# Cytrill.net
KiCad netlist of a schematic drawn in EAGLE
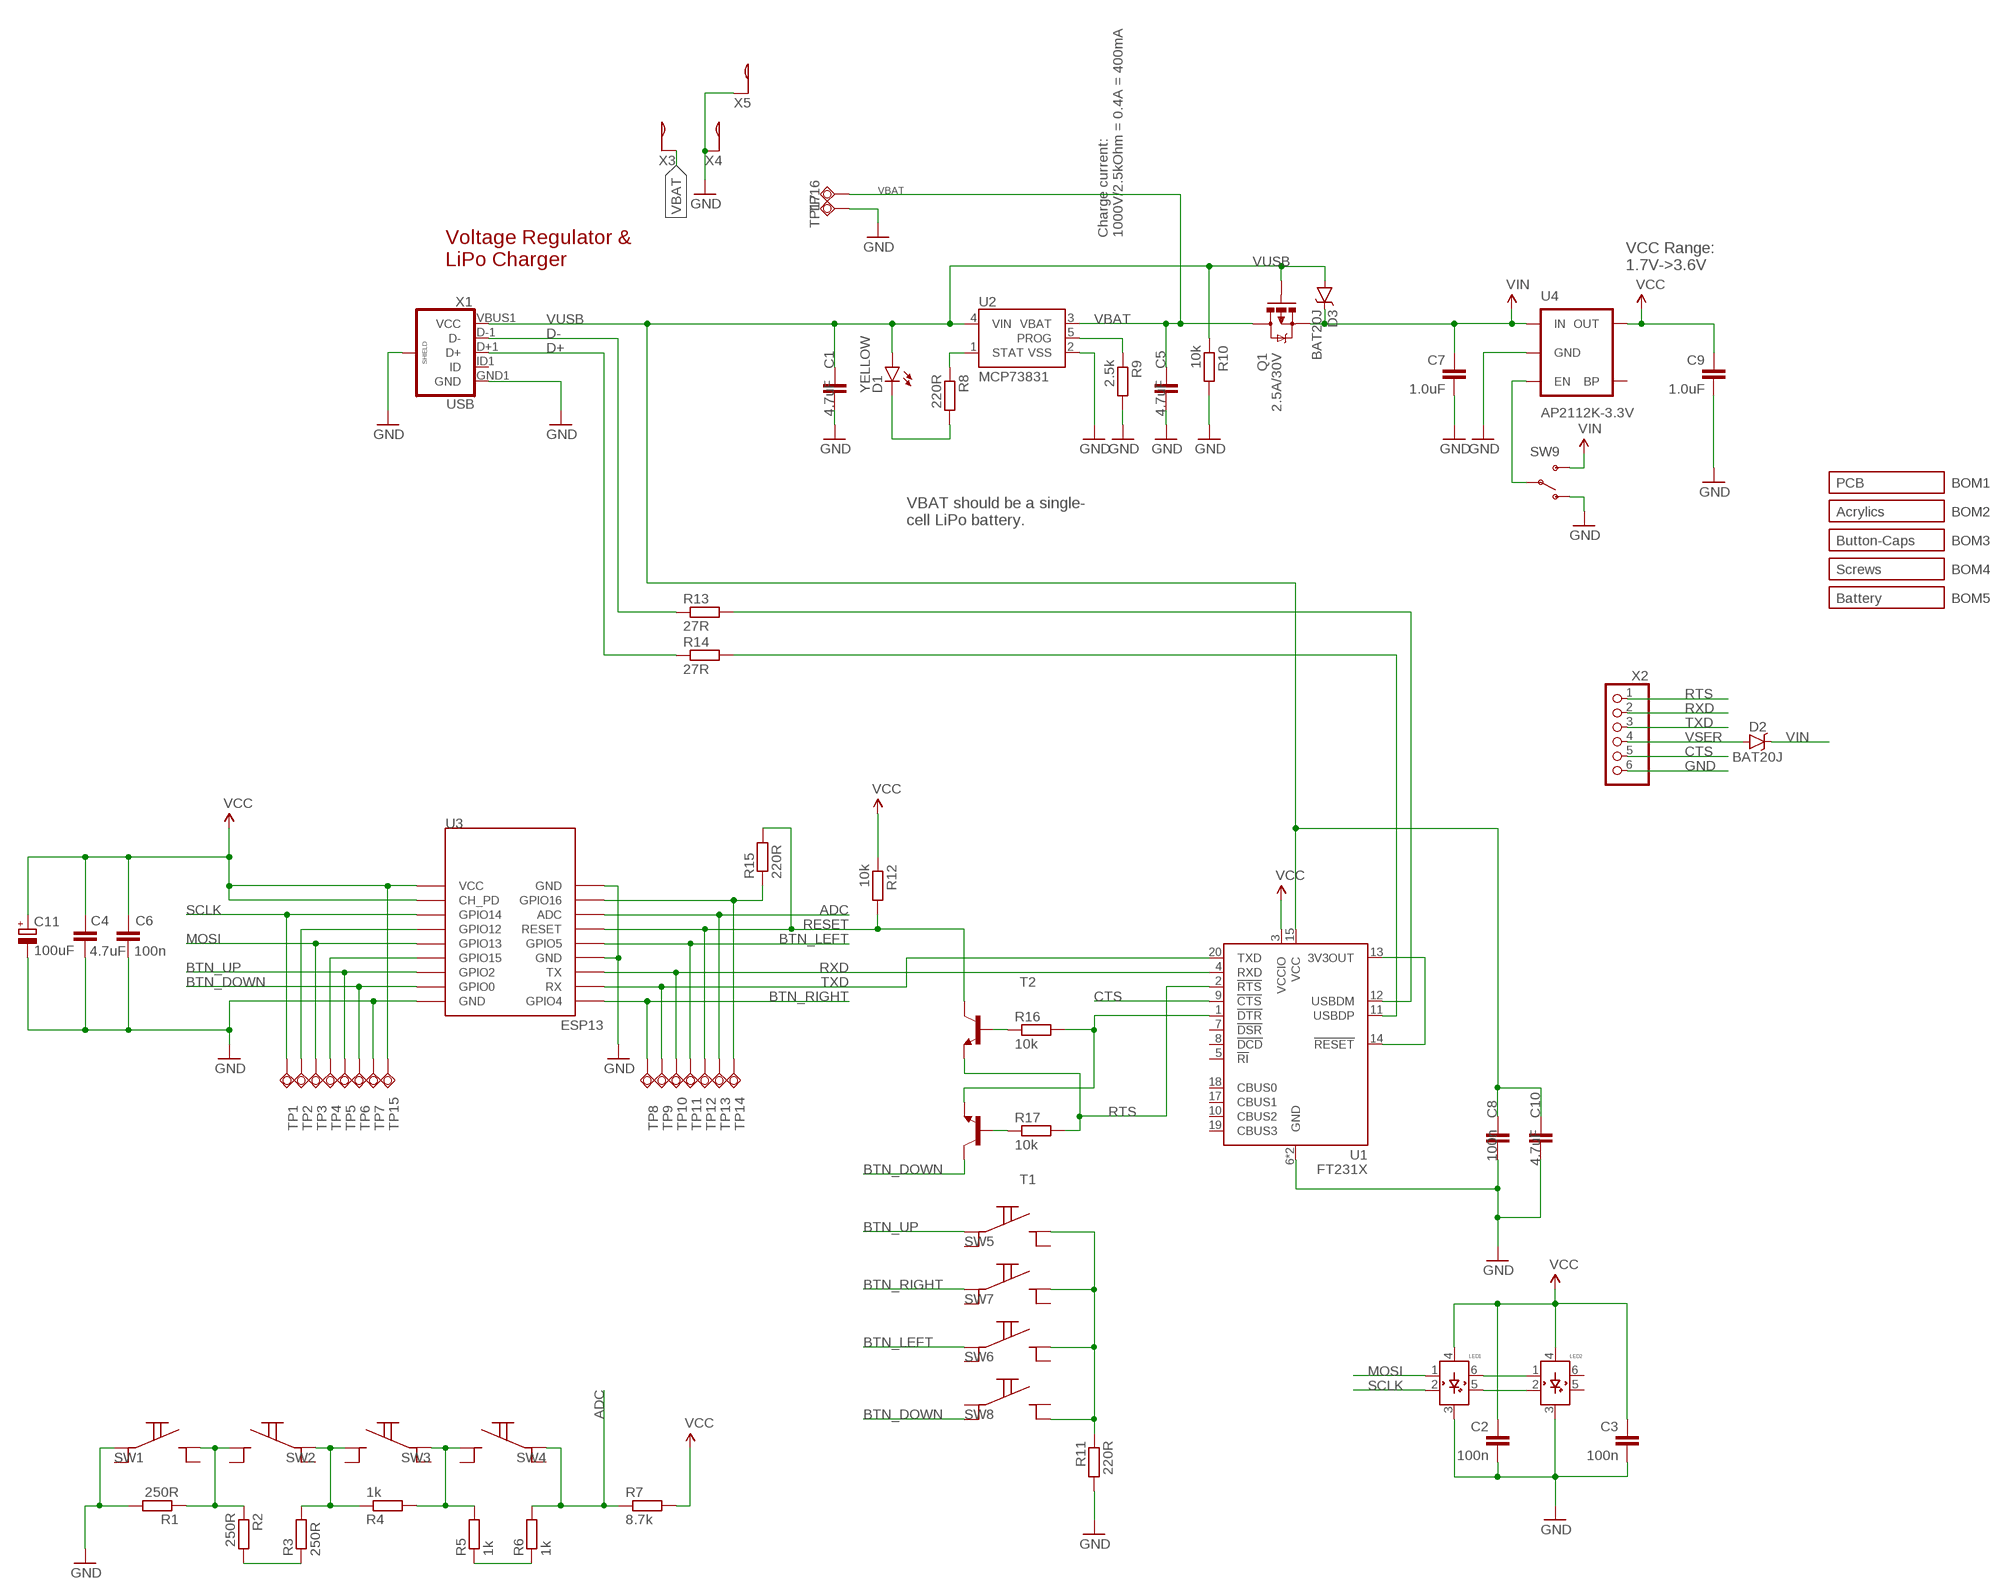
[diagram p0: schematic, sheet 1]

(export (version "E")
  (design (tool "Eeschema 10.0.6"))
  (components
    (comp (ref "C1")
      (value "4.7uF")
      (footprint "eagle-import:C0603")
      (fields (field (name "PARTNO") "GRM188R61A475KE15D-MO"))
      (libsource (lib "eagle-import") (part "C-EUC0603"))
    )
    (comp (ref "C2")
      (value "100n")
      (footprint "eagle-import:C0603")
      (fields (field (name "PARTNO") "C0603C104K4RACTU-MO"))
      (libsource (lib "eagle-import") (part "C-EUC0603"))
    )
    (comp (ref "C3")
      (value "100n")
      (footprint "eagle-import:C0603")
      (fields (field (name "PARTNO") "C0603C104K4RACTU-MO"))
      (libsource (lib "eagle-import") (part "C-EUC0603"))
    )
    (comp (ref "C4")
      (value "4.7uF")
      (footprint "eagle-import:C0603")
      (fields (field (name "PARTNO") "GRM188R61A475KE15D-MO"))
      (libsource (lib "eagle-import") (part "C-EUC0603"))
    )
    (comp (ref "C5")
      (value "4.7uF")
      (footprint "eagle-import:C0603")
      (fields (field (name "PARTNO") "GRM188R61A475KE15D-MO"))
      (libsource (lib "eagle-import") (part "C-EUC0603"))
    )
    (comp (ref "C6")
      (value "100n")
      (footprint "eagle-import:C0603")
      (fields (field (name "PARTNO") "C0603C104K4RACTU-MO"))
      (libsource (lib "eagle-import") (part "C-EUC0603"))
    )
    (comp (ref "C7")
      (value "1.0uF")
      (footprint "eagle-import:C0603")
      (fields (field (name "PARTNO") "GRM188R61E105KA12D-MO"))
      (libsource (lib "eagle-import") (part "C-EUC0603"))
    )
    (comp (ref "C8")
      (value "100n")
      (footprint "eagle-import:C0603")
      (fields (field (name "PARTNO") "C0603C104K4RACTU-MO"))
      (libsource (lib "eagle-import") (part "C-EUC0603"))
    )
    (comp (ref "C9")
      (value "1.0uF")
      (footprint "eagle-import:C0603")
      (fields (field (name "PARTNO") "GRM188R61E105KA12D-MO"))
      (libsource (lib "eagle-import") (part "C-EUC0603"))
    )
    (comp (ref "C10")
      (value "4.7uF")
      (footprint "eagle-import:C0603")
      (fields (field (name "PARTNO") "GRM188R61A475KE15D-MO"))
      (libsource (lib "eagle-import") (part "C-EUC0603"))
    )
    (comp (ref "C11")
      (value "100uF")
      (footprint "eagle-import:3216-A")
      (fields (field (name "PARTNO") "TANTAL100UF"))
      (libsource (lib "eagle-import") (part "CPOL-EU085CS-1AR"))
    )
    (comp (ref "D1")
      (value "YELLOW")
      (footprint "eagle-import:LED-0603")
      (fields (field (name "PARTNO") "LYQ396P1Q236-MO"))
      (libsource (lib "eagle-import") (part "LED-YELLOW0603"))
    )
    (comp (ref "D2")
      (value "BAT20J")
      (footprint "eagle-import:SOD-323")
      (fields (field (name "PARTNO") "BAT20JFILM-MO"))
      (libsource (lib "eagle-import") (part "DIODE-SCHOTTKY-BAT20J"))
    )
    (comp (ref "D3")
      (value "BAT20J")
      (footprint "eagle-import:SOD-323")
      (fields (field (name "PARTNO") "BAT20JFILM-MO"))
      (libsource (lib "eagle-import") (part "DIODE-SCHOTTKY-BAT20J"))
    )
    (comp (ref "LED1")
      (value "APA102")
      (footprint "eagle-import:RGBLED5050")
      (libsource (lib "eagle-import") (part "APA102"))
    )
    (comp (ref "LED2")
      (value "APA102")
      (footprint "eagle-import:RGBLED5050")
      (libsource (lib "eagle-import") (part "APA102"))
    )
    (comp (ref "Q1")
      (value "2.5A/30V")
      (footprint "eagle-import:SOT23-3")
      (fields (field (name "PARTNO") "DMP3130L-7-MO"))
      (libsource (lib "eagle-import") (part "MOSFET-PCHANNELDMG2307L"))
    )
    (comp (ref "R1")
      (value "250R")
      (footprint "eagle-import:R0603")
      (fields (field (name "PARTNO") "ERJ3EKF2490V-MO"))
      (libsource (lib "eagle-import") (part "R-EU_R0603"))
    )
    (comp (ref "R2")
      (value "250R")
      (footprint "eagle-import:R0603")
      (fields (field (name "PARTNO") "ERJ3EKF2490V-MO"))
      (libsource (lib "eagle-import") (part "R-EU_R0603"))
    )
    (comp (ref "R3")
      (value "250R")
      (footprint "eagle-import:R0603")
      (fields (field (name "PARTNO") "ERJ3EKF2490V-MO"))
      (libsource (lib "eagle-import") (part "R-EU_R0603"))
    )
    (comp (ref "R4")
      (value "1k")
      (footprint "eagle-import:R0603")
      (fields (field (name "PARTNO") "ERJ3EKF1001V-MO"))
      (libsource (lib "eagle-import") (part "R-EU_R0603"))
    )
    (comp (ref "R5")
      (value "1k")
      (footprint "eagle-import:R0603")
      (fields (field (name "PARTNO") "ERJ3EKF1001V-MO"))
      (libsource (lib "eagle-import") (part "R-EU_R0603"))
    )
    (comp (ref "R6")
      (value "1k")
      (footprint "eagle-import:R0603")
      (fields (field (name "PARTNO") "ERJ3EKF1001V-MO"))
      (libsource (lib "eagle-import") (part "R-EU_R0603"))
    )
    (comp (ref "R7")
      (value "8.7k")
      (footprint "eagle-import:R0603")
      (fields (field (name "PARTNO") "ERJ3EKF8661V-MO"))
      (libsource (lib "eagle-import") (part "R-EU_R0603"))
    )
    (comp (ref "R8")
      (value "220R")
      (footprint "eagle-import:R0603")
      (fields (field (name "PARTNO") "ERJ3EKF2200V-MO"))
      (libsource (lib "eagle-import") (part "R-EU_R0603"))
    )
    (comp (ref "R9")
      (value "2.5k")
      (footprint "eagle-import:R0603")
      (fields (field (name "PARTNO") "ERJ3EKF2491V-MO"))
      (libsource (lib "eagle-import") (part "R-EU_R0603"))
    )
    (comp (ref "R10")
      (value "10k")
      (footprint "eagle-import:R0603")
      (fields (field (name "PARTNO") "ERJ3EKF1002V-MO"))
      (libsource (lib "eagle-import") (part "R-EU_R0603"))
    )
    (comp (ref "R11")
      (value "220R")
      (footprint "eagle-import:R0603")
      (fields (field (name "PARTNO") "ERJ3EKF2200V-MO"))
      (libsource (lib "eagle-import") (part "R-EU_R0603"))
    )
    (comp (ref "R12")
      (value "10k")
      (footprint "eagle-import:R0603")
      (fields (field (name "PARTNO") "ERJ3EKF1002V-MO"))
      (libsource (lib "eagle-import") (part "R-EU_R0603"))
    )
    (comp (ref "R13")
      (value "27R")
      (footprint "eagle-import:R0603")
      (fields (field (name "PARTNO") "ERJ3EKF27R0V-MO"))
      (libsource (lib "eagle-import") (part "R-EU_R0603"))
    )
    (comp (ref "R14")
      (value "27R")
      (footprint "eagle-import:R0603")
      (fields (field (name "PARTNO") "ERJ3EKF27R0V-MO"))
      (libsource (lib "eagle-import") (part "R-EU_R0603"))
    )
    (comp (ref "R15")
      (value "220R")
      (footprint "eagle-import:R0603")
      (fields (field (name "PARTNO") "ERJ3EKF2200V-MO"))
      (libsource (lib "eagle-import") (part "R-EU_R0603"))
    )
    (comp (ref "R16")
      (value "10k")
      (footprint "eagle-import:R0603")
      (fields (field (name "PARTNO") "ERJ3EKF1002V-MO"))
      (libsource (lib "eagle-import") (part "R-EU_R0603"))
    )
    (comp (ref "R17")
      (value "10k")
      (footprint "eagle-import:R0603")
      (fields (field (name "PARTNO") "ERJ3EKF1002V-MO"))
      (libsource (lib "eagle-import") (part "R-EU_R0603"))
    )
    (comp (ref "SW1")
      (value "TACTSWITCH6MM")
      (footprint "eagle-import:TACTSWITCH")
      (fields (field (name "PARTNO") "101-0364-EV-MO"))
      (libsource (lib "eagle-import") (part "TACTSWITCH6MM"))
    )
    (comp (ref "SW2")
      (value "TACTSWITCH6MM")
      (footprint "eagle-import:TACTSWITCH")
      (fields (field (name "PARTNO") "101-0364-EV-MO"))
      (libsource (lib "eagle-import") (part "TACTSWITCH6MM"))
    )
    (comp (ref "SW3")
      (value "TACTSWITCH6MM")
      (footprint "eagle-import:TACTSWITCH")
      (fields (field (name "PARTNO") "101-0364-EV-MO"))
      (libsource (lib "eagle-import") (part "TACTSWITCH6MM"))
    )
    (comp (ref "SW4")
      (value "TACTSWITCH6MM")
      (footprint "eagle-import:TACTSWITCH")
      (fields (field (name "PARTNO") "101-0364-EV-MO"))
      (libsource (lib "eagle-import") (part "TACTSWITCH6MM"))
    )
    (comp (ref "SW5")
      (value "TACTSWITCH6MM")
      (footprint "eagle-import:TACTSWITCH")
      (fields (field (name "PARTNO") "101-0364-EV-MO"))
      (libsource (lib "eagle-import") (part "TACTSWITCH6MM"))
    )
    (comp (ref "SW6")
      (value "TACTSWITCH6MM")
      (footprint "eagle-import:TACTSWITCH")
      (fields (field (name "PARTNO") "101-0364-EV-MO"))
      (libsource (lib "eagle-import") (part "TACTSWITCH6MM"))
    )
    (comp (ref "SW7")
      (value "TACTSWITCH6MM")
      (footprint "eagle-import:TACTSWITCH")
      (fields (field (name "PARTNO") "101-0364-EV-MO"))
      (libsource (lib "eagle-import") (part "TACTSWITCH6MM"))
    )
    (comp (ref "SW8")
      (value "TACTSWITCH6MM")
      (footprint "eagle-import:TACTSWITCH")
      (fields (field (name "PARTNO") "101-0364-EV-MO"))
      (libsource (lib "eagle-import") (part "TACTSWITCH6MM"))
    )
    (comp (ref "SW9")
      (value "SWITCH-SPDT-SMD-A")
      (footprint "eagle-import:SWITCH-SPST-SMD-A")
      (fields (field (name "PARTNO") "SSSS810701"))
      (libsource (lib "eagle-import") (part "SWITCH-SPDT-SMD-A"))
    )
    (comp (ref "T1")
      (value "BC847C-NPN-SOT23-BEC")
      (footprint "eagle-import:SOT23-BEC")
      (fields (field (name "PARTNO") "BC847C-MO"))
      (libsource (lib "eagle-import") (part "-NPN-SOT23-BECBC847C"))
    )
    (comp (ref "T2")
      (value "BC847C-NPN-SOT23-BEC")
      (footprint "eagle-import:SOT23-BEC")
      (fields (field (name "PARTNO") "BC847C-MO"))
      (libsource (lib "eagle-import") (part "-NPN-SOT23-BECBC847C"))
    )
    (comp (ref "TP1")
      (value "TPSQTP15SQ")
      (footprint "eagle-import:TP15SQ")
      (fields (field (name "PARTNO") "TESTPAD"))
      (libsource (lib "eagle-import") (part "TPSQTP15SQ"))
    )
    (comp (ref "TP2")
      (value "TPSQTP15SQ")
      (footprint "eagle-import:TP15SQ")
      (fields (field (name "PARTNO") "TESTPAD"))
      (libsource (lib "eagle-import") (part "TPSQTP15SQ"))
    )
    (comp (ref "TP3")
      (value "TPSQTP15SQ")
      (footprint "eagle-import:TP15SQ")
      (fields (field (name "PARTNO") "TESTPAD"))
      (libsource (lib "eagle-import") (part "TPSQTP15SQ"))
    )
    (comp (ref "TP4")
      (value "TPSQTP15SQ")
      (footprint "eagle-import:TP15SQ")
      (fields (field (name "PARTNO") "TESTPAD"))
      (libsource (lib "eagle-import") (part "TPSQTP15SQ"))
    )
    (comp (ref "TP5")
      (value "TPSQTP15SQ")
      (footprint "eagle-import:TP15SQ")
      (fields (field (name "PARTNO") "TESTPAD"))
      (libsource (lib "eagle-import") (part "TPSQTP15SQ"))
    )
    (comp (ref "TP6")
      (value "TPSQTP15SQ")
      (footprint "eagle-import:TP15SQ")
      (fields (field (name "PARTNO") "TESTPAD"))
      (libsource (lib "eagle-import") (part "TPSQTP15SQ"))
    )
    (comp (ref "TP7")
      (value "TPSQTP15SQ")
      (footprint "eagle-import:TP15SQ")
      (fields (field (name "PARTNO") "TESTPAD"))
      (libsource (lib "eagle-import") (part "TPSQTP15SQ"))
    )
    (comp (ref "TP8")
      (value "TPSQTP15SQ")
      (footprint "eagle-import:TP15SQ")
      (fields (field (name "PARTNO") "TESTPAD"))
      (libsource (lib "eagle-import") (part "TPSQTP15SQ"))
    )
    (comp (ref "TP9")
      (value "TPSQTP15SQ")
      (footprint "eagle-import:TP15SQ")
      (fields (field (name "PARTNO") "TESTPAD"))
      (libsource (lib "eagle-import") (part "TPSQTP15SQ"))
    )
    (comp (ref "TP10")
      (value "TPSQTP15SQ")
      (footprint "eagle-import:TP15SQ")
      (fields (field (name "PARTNO") "TESTPAD"))
      (libsource (lib "eagle-import") (part "TPSQTP15SQ"))
    )
    (comp (ref "TP11")
      (value "TPSQTP15SQ")
      (footprint "eagle-import:TP15SQ")
      (fields (field (name "PARTNO") "TESTPAD"))
      (libsource (lib "eagle-import") (part "TPSQTP15SQ"))
    )
    (comp (ref "TP12")
      (value "TPSQTP15SQ")
      (footprint "eagle-import:TP15SQ")
      (fields (field (name "PARTNO") "TESTPAD"))
      (libsource (lib "eagle-import") (part "TPSQTP15SQ"))
    )
    (comp (ref "TP13")
      (value "TPSQTP15SQ")
      (footprint "eagle-import:TP15SQ")
      (fields (field (name "PARTNO") "TESTPAD"))
      (libsource (lib "eagle-import") (part "TPSQTP15SQ"))
    )
    (comp (ref "TP14")
      (value "TPSQTP15SQ")
      (footprint "eagle-import:TP15SQ")
      (fields (field (name "PARTNO") "TESTPAD"))
      (libsource (lib "eagle-import") (part "TPSQTP15SQ"))
    )
    (comp (ref "TP15")
      (value "TPSQTP15SQ")
      (footprint "eagle-import:TP15SQ")
      (fields (field (name "PARTNO") "TESTPAD"))
      (libsource (lib "eagle-import") (part "TPSQTP15SQ"))
    )
    (comp (ref "TP16")
      (value "TPSQTP20R")
      (footprint "eagle-import:TP20R")
      (fields (field (name "PARTNO") "TESTPAD"))
      (libsource (lib "eagle-import") (part "TPSQTP20R"))
    )
    (comp (ref "TP17")
      (value "TPSQTP20R")
      (footprint "eagle-import:TP20R")
      (fields (field (name "PARTNO") "TESTPAD"))
      (libsource (lib "eagle-import") (part "TPSQTP20R"))
    )
    (comp (ref "U1")
      (value "FT231X")
      (footprint "eagle-import:SSOP20")
      (fields (field (name "PARTNO") "FT231XS"))
      (libsource (lib "eagle-import") (part "FT231X"))
    )
    (comp (ref "U2")
      (value "MCP73831")
      (footprint "eagle-import:SOT23-5")
      (fields (field (name "PARTNO") "MCP73831T-2ATI/OT"))
      (libsource (lib "eagle-import") (part "MCP73831"))
    )
    (comp (ref "U3")
      (value "ESP13")
      (footprint "eagle-import:ESP13")
      (fields (field (name "PARTNO") "esp-13"))
      (libsource (lib "eagle-import") (part "ESP13"))
    )
    (comp (ref "U4")
      (value "AP2112K-3.3V")
      (footprint "eagle-import:SOT23-5")
      (fields (field (name "PARTNO") "AP2112K-3.3"))
      (libsource (lib "eagle-import") (part "V_REG_LDOSMD"))
    )
    (comp (ref "X1")
      (value "USB")
      (footprint "eagle-import:USB-B-MICRO-SMD_V03")
      (libsource (lib "eagle-import") (part "USB_MICROB_PLUGCONN-11752"))
    )
    (comp (ref "X2")
      (value "PINHD-1X6/90-SMD")
      (footprint "eagle-import:1X06_90-SMD")
      (fields (field (name "PARTNO") "961106-5500-AR-PR-MO"))
      (libsource (lib "eagle-import") (part "PINHD-1X6/90-SMD"))
    )
    (comp (ref "X3")
      (value "BATTERYTERMINAL")
      (footprint "eagle-import:KEYSTONE-55")
      (fields (field (name "PARTNO") "KS55-MO"))
      (libsource (lib "eagle-import") (part "BATTERYTERMINAL"))
    )
    (comp (ref "X4")
      (value "BATTERYTERMINAL")
      (footprint "eagle-import:KEYSTONE-55")
      (fields (field (name "PARTNO") "KS55-MO"))
      (libsource (lib "eagle-import") (part "BATTERYTERMINAL"))
    )
    (comp (ref "X5")
      (value "BATTERYTERMINAL")
      (footprint "eagle-import:KEYSTONE-55")
      (fields (field (name "PARTNO") "KS55-MO"))
      (libsource (lib "eagle-import") (part "BATTERYTERMINAL"))
    )
  )
  (nets
    (net (code "1") (name "/ADC") (class "Default")
      (node (ref "R6") (pin "2") (pinfunction "2_2") (pintype "passive"))
      (node (ref "R7") (pin "1") (pinfunction "1_1") (pintype "passive"))
      (node (ref "SW4") (pin "A@1") (pinfunction "A_A@1") (pintype "bidirectional"))
      (node (ref "TP13") (pin "TP") (pinfunction "TP_TP") (pintype "input"))
      (node (ref "U3") (pin "ADC") (pinfunction "ADC_ADC") (pintype "bidirectional"))
    )
    (net (code "2") (name "/BTN_DOWN") (class "Default")
      (node (ref "SW8") (pin "A@2") (pinfunction "A1_A@2") (pintype "bidirectional"))
      (node (ref "T1") (pin "3") (pinfunction "C_3") (pintype "passive"))
      (node (ref "TP6") (pin "TP") (pinfunction "TP_TP") (pintype "input"))
      (node (ref "U3") (pin "GPIO0") (pinfunction "GPIO0_GPIO0") (pintype "bidirectional"))
    )
    (net (code "3") (name "/BTN_LEFT") (class "Default")
      (node (ref "SW6") (pin "A@1") (pinfunction "A_A@1") (pintype "bidirectional"))
      (node (ref "TP11") (pin "TP") (pinfunction "TP_TP") (pintype "input"))
      (node (ref "U3") (pin "GPIO5") (pinfunction "GPIO5_GPIO5") (pintype "bidirectional"))
    )
    (net (code "4") (name "/BTN_RIGHT") (class "Default")
      (node (ref "SW7") (pin "A@1") (pinfunction "A_A@1") (pintype "bidirectional"))
      (node (ref "TP8") (pin "TP") (pinfunction "TP_TP") (pintype "input"))
      (node (ref "U3") (pin "GPIO4") (pinfunction "GPIO4_GPIO4") (pintype "bidirectional"))
    )
    (net (code "5") (name "/BTN_UP") (class "Default")
      (node (ref "SW5") (pin "A@1") (pinfunction "A_A@1") (pintype "bidirectional"))
      (node (ref "TP5") (pin "TP") (pinfunction "TP_TP") (pintype "input"))
      (node (ref "U3") (pin "GPIO2") (pinfunction "GPIO2_GPIO2") (pintype "bidirectional"))
    )
    (net (code "6") (name "/CTS") (class "Default")
      (node (ref "U1") (pin "9") (pinfunction "~{CTS}_9") (pintype "input"))
      (node (ref "X2") (pin "5") (pinfunction "5_5") (pintype "passive"))
    )
    (net (code "7") (name "/D+") (class "Default")
      (node (ref "R14") (pin "1") (pinfunction "1_1") (pintype "passive"))
      (node (ref "X1") (pin "D+1") (pinfunction "D+_D+1") (pintype "bidirectional"))
    )
    (net (code "8") (name "/D-") (class "Default")
      (node (ref "R13") (pin "1") (pinfunction "1_1") (pintype "passive"))
      (node (ref "X1") (pin "D-1") (pinfunction "D-_D-1") (pintype "bidirectional"))
    )
    (net (code "9") (name "/MOSI") (class "Default")
      (node (ref "LED1") (pin "1") (pinfunction "DIN_1") (pintype "input"))
      (node (ref "TP3") (pin "TP") (pinfunction "TP_TP") (pintype "input"))
      (node (ref "U3") (pin "GPIO13") (pinfunction "GPIO13_GPIO13") (pintype "bidirectional"))
    )
    (net (code "10") (name "/RESET") (class "Default")
      (node (ref "R12") (pin "2") (pinfunction "2_2") (pintype "passive"))
      (node (ref "R15") (pin "2") (pinfunction "2_2") (pintype "passive"))
      (node (ref "T2") (pin "3") (pinfunction "C_3") (pintype "passive"))
      (node (ref "TP12") (pin "TP") (pinfunction "TP_TP") (pintype "input"))
      (node (ref "U3") (pin "RST") (pinfunction "RESET_RST") (pintype "bidirectional"))
    )
    (net (code "11") (name "/RTS") (class "Default")
      (node (ref "R17") (pin "2") (pinfunction "2_2") (pintype "passive"))
      (node (ref "T2") (pin "2") (pinfunction "E_2") (pintype "passive"))
      (node (ref "U1") (pin "2") (pinfunction "~{RTS}_2") (pintype "output"))
      (node (ref "X2") (pin "1") (pinfunction "1_1") (pintype "passive"))
    )
    (net (code "12") (name "/RXD") (class "Default")
      (node (ref "TP10") (pin "TP") (pinfunction "TP_TP") (pintype "input"))
      (node (ref "U1") (pin "4") (pinfunction "RXD_4") (pintype "input"))
      (node (ref "U3") (pin "TXD") (pinfunction "TX_TXD") (pintype "bidirectional"))
      (node (ref "X2") (pin "2") (pinfunction "2_2") (pintype "passive"))
    )
    (net (code "13") (name "/SCLK") (class "Default")
      (node (ref "LED1") (pin "2") (pinfunction "CIN_2") (pintype "input"))
      (node (ref "TP1") (pin "TP") (pinfunction "TP_TP") (pintype "input"))
      (node (ref "U3") (pin "GPIO14") (pinfunction "GPIO14_GPIO14") (pintype "bidirectional"))
    )
    (net (code "14") (name "/TXD") (class "Default")
      (node (ref "TP9") (pin "TP") (pinfunction "TP_TP") (pintype "input"))
      (node (ref "U1") (pin "20") (pinfunction "TXD_20") (pintype "output"))
      (node (ref "U3") (pin "RXD") (pinfunction "RX_RXD") (pintype "bidirectional"))
      (node (ref "X2") (pin "3") (pinfunction "3_3") (pintype "passive"))
    )
    (net (code "15") (name "/VSER") (class "Default")
      (node (ref "D2") (pin "A") (pinfunction "A_A") (pintype "passive"))
      (node (ref "X2") (pin "4") (pinfunction "4_4") (pintype "passive"))
    )
    (net (code "16") (name "/VUSB") (class "Default")
      (node (ref "C1") (pin "1") (pinfunction "1_1") (pintype "passive"))
      (node (ref "C10") (pin "1") (pinfunction "1_1") (pintype "passive"))
      (node (ref "C8") (pin "1") (pinfunction "1_1") (pintype "passive"))
      (node (ref "D1") (pin "A") (pinfunction "A_A") (pintype "passive"))
      (node (ref "D3") (pin "A") (pinfunction "A_A") (pintype "passive"))
      (node (ref "Q1") (pin "1") (pinfunction "G_1") (pintype "passive"))
      (node (ref "R10") (pin "1") (pinfunction "1_1") (pintype "passive"))
      (node (ref "U1") (pin "15") (pinfunction "VCC_15") (pintype "power_in"))
      (node (ref "U2") (pin "4") (pinfunction "VIN_4") (pintype "power_in"))
      (node (ref "X1") (pin "VBUS1") (pinfunction "VCC_VBUS1") (pintype "bidirectional"))
    )
    (net (code "17") (name "GND") (class "Default")
      (node (ref "C1") (pin "2") (pinfunction "2_2") (pintype "passive"))
      (node (ref "C10") (pin "2") (pinfunction "2_2") (pintype "passive"))
      (node (ref "C11") (pin "-") (pinfunction "-_-") (pintype "passive"))
      (node (ref "C2") (pin "2") (pinfunction "2_2") (pintype "passive"))
      (node (ref "C3") (pin "2") (pinfunction "2_2") (pintype "passive"))
      (node (ref "C4") (pin "2") (pinfunction "2_2") (pintype "passive"))
      (node (ref "C5") (pin "2") (pinfunction "2_2") (pintype "passive"))
      (node (ref "C6") (pin "2") (pinfunction "2_2") (pintype "passive"))
      (node (ref "C7") (pin "2") (pinfunction "2_2") (pintype "passive"))
      (node (ref "C8") (pin "2") (pinfunction "2_2") (pintype "passive"))
      (node (ref "C9") (pin "2") (pinfunction "2_2") (pintype "passive"))
      (node (ref "LED1") (pin "3") (pinfunction "GND_3") (pintype "bidirectional"))
      (node (ref "LED2") (pin "3") (pinfunction "GND_3") (pintype "bidirectional"))
      (node (ref "R1") (pin "2") (pinfunction "2_2") (pintype "passive"))
      (node (ref "R10") (pin "2") (pinfunction "2_2") (pintype "passive"))
      (node (ref "R11") (pin "2") (pinfunction "2_2") (pintype "passive"))
      (node (ref "R9") (pin "2") (pinfunction "2_2") (pintype "passive"))
      (node (ref "SW1") (pin "A@1") (pinfunction "A_A@1") (pintype "bidirectional"))
      (node (ref "SW9") (pin "1") (pinfunction "O_1") (pintype "passive"))
      (node (ref "TP17") (pin "TP") (pinfunction "TP_TP") (pintype "input"))
      (node (ref "TP7") (pin "TP") (pinfunction "TP_TP") (pintype "input"))
      (node (ref "U1") (pin "16") (pinfunction "GND_16") (pintype "power_in"))
      (node (ref "U1") (pin "6") (pinfunction "GND_6") (pintype "power_in"))
      (node (ref "U2") (pin "2") (pinfunction "VSS_2") (pintype "power_in"))
      (node (ref "U3") (pin "GND@0") (pinfunction "GND_GND@0") (pintype "bidirectional"))
      (node (ref "U3") (pin "GND@1") (pinfunction "GND_GND@1") (pintype "bidirectional"))
      (node (ref "U3") (pin "GND@2") (pinfunction "GND_GND@2") (pintype "bidirectional"))
      (node (ref "U4") (pin "2") (pinfunction "GND_2") (pintype "input"))
      (node (ref "X1") (pin "GND1") (pinfunction "GND_GND1") (pintype "bidirectional"))
      (node (ref "X1") (pin "SHIELD1") (pinfunction "SHIELD_SHIELD1") (pintype "bidirectional"))
      (node (ref "X1") (pin "SHIELD2") (pinfunction "SHIELD_SHIELD2") (pintype "bidirectional"))
      (node (ref "X2") (pin "6") (pinfunction "6_6") (pintype "passive"))
      (node (ref "X4") (pin "1@1") (pinfunction "P$1_1@1") (pintype "bidirectional"))
      (node (ref "X4") (pin "1@2") (pinfunction "P$1_1@2") (pintype "bidirectional"))
      (node (ref "X5") (pin "1@1") (pinfunction "P$1_1@1") (pintype "bidirectional"))
      (node (ref "X5") (pin "1@2") (pinfunction "P$1_1@2") (pintype "bidirectional"))
    )
    (net (code "18") (name "Net-(D1-PadC)") (class "Default")
      (node (ref "D1") (pin "C") (pinfunction "C_C") (pintype "passive"))
      (node (ref "R8") (pin "2") (pinfunction "2_2") (pintype "passive"))
    )
    (net (code "19") (name "Net-(LED1-COUT)") (class "Default")
      (node (ref "LED1") (pin "5") (pinfunction "COUT_5") (pintype "output"))
      (node (ref "LED2") (pin "2") (pinfunction "CIN_2") (pintype "input"))
    )
    (net (code "20") (name "Net-(LED1-DOUT)") (class "Default")
      (node (ref "LED1") (pin "6") (pinfunction "DOUT_6") (pintype "output"))
      (node (ref "LED2") (pin "1") (pinfunction "DIN_1") (pintype "input"))
    )
    (net (code "21") (name "Net-(R2-Pad2)") (class "Default")
      (node (ref "R2") (pin "2") (pinfunction "2_2") (pintype "passive"))
      (node (ref "R3") (pin "1") (pinfunction "1_1") (pintype "passive"))
    )
    (net (code "22") (name "Net-(R5-Pad1)") (class "Default")
      (node (ref "R5") (pin "1") (pinfunction "1_1") (pintype "passive"))
      (node (ref "R6") (pin "1") (pinfunction "1_1") (pintype "passive"))
    )
    (net (code "23") (name "Net-(R15-Pad1)") (class "Default")
      (node (ref "R15") (pin "1") (pinfunction "1_1") (pintype "passive"))
      (node (ref "TP14") (pin "TP") (pinfunction "TP_TP") (pintype "input"))
      (node (ref "U3") (pin "GPIO16") (pinfunction "GPIO16_GPIO16") (pintype "bidirectional"))
    )
    (net (code "24") (name "Net-(SW1-B)") (class "Default")
      (node (ref "R1") (pin "1") (pinfunction "1_1") (pintype "passive"))
      (node (ref "R2") (pin "1") (pinfunction "1_1") (pintype "passive"))
      (node (ref "SW1") (pin "B@1") (pinfunction "B_B@1") (pintype "bidirectional"))
      (node (ref "SW2") (pin "B@1") (pinfunction "B_B@1") (pintype "bidirectional"))
    )
    (net (code "25") (name "Net-(SW2-A)") (class "Default")
      (node (ref "R3") (pin "2") (pinfunction "2_2") (pintype "passive"))
      (node (ref "R4") (pin "1") (pinfunction "1_1") (pintype "passive"))
      (node (ref "SW2") (pin "A@1") (pinfunction "A_A@1") (pintype "bidirectional"))
      (node (ref "SW3") (pin "B@1") (pinfunction "B_B@1") (pintype "bidirectional"))
    )
    (net (code "26") (name "Net-(SW3-A)") (class "Default")
      (node (ref "R4") (pin "2") (pinfunction "2_2") (pintype "passive"))
      (node (ref "R5") (pin "2") (pinfunction "2_2") (pintype "passive"))
      (node (ref "SW3") (pin "A@1") (pinfunction "A_A@1") (pintype "bidirectional"))
      (node (ref "SW4") (pin "B@1") (pinfunction "B_B@1") (pintype "bidirectional"))
    )
    (net (code "27") (name "Net-(SW5-B)") (class "Default")
      (node (ref "R11") (pin "1") (pinfunction "1_1") (pintype "passive"))
      (node (ref "SW5") (pin "B@1") (pinfunction "B_B@1") (pintype "bidirectional"))
      (node (ref "SW6") (pin "B@1") (pinfunction "B_B@1") (pintype "bidirectional"))
      (node (ref "SW7") (pin "B@1") (pinfunction "B_B@1") (pintype "bidirectional"))
      (node (ref "SW8") (pin "B@2") (pinfunction "B1_B@2") (pintype "bidirectional"))
    )
    (net (code "28") (name "Net-(SW9-P)") (class "Default")
      (node (ref "SW9") (pin "2") (pinfunction "P_2") (pintype "passive"))
      (node (ref "U4") (pin "3") (pinfunction "EN_3") (pintype "input"))
    )
    (net (code "29") (name "Net-(T1-B)") (class "Default")
      (node (ref "R17") (pin "1") (pinfunction "1_1") (pintype "passive"))
      (node (ref "T1") (pin "1") (pinfunction "B_1") (pintype "passive"))
    )
    (net (code "30") (name "Net-(T1-E)") (class "Default")
      (node (ref "R16") (pin "2") (pinfunction "2_2") (pintype "passive"))
      (node (ref "T1") (pin "2") (pinfunction "E_2") (pintype "passive"))
      (node (ref "U1") (pin "1") (pinfunction "~{DTR}_1") (pintype "input"))
    )
    (net (code "31") (name "Net-(T2-B)") (class "Default")
      (node (ref "R16") (pin "1") (pinfunction "1_1") (pintype "passive"))
      (node (ref "T2") (pin "1") (pinfunction "B_1") (pintype "passive"))
    )
    (net (code "32") (name "Net-(TP2-PadTP)") (class "Default")
      (node (ref "TP2") (pin "TP") (pinfunction "TP_TP") (pintype "input"))
      (node (ref "U3") (pin "GPIO12") (pinfunction "GPIO12_GPIO12") (pintype "bidirectional"))
    )
    (net (code "33") (name "Net-(TP4-PadTP)") (class "Default")
      (node (ref "TP4") (pin "TP") (pinfunction "TP_TP") (pintype "input"))
      (node (ref "U3") (pin "GPIO15") (pinfunction "GPIO15_GPIO15") (pintype "bidirectional"))
    )
    (net (code "34") (name "Net-(U1-3V3OUT)") (class "Default")
      (node (ref "U1") (pin "13") (pinfunction "3V3OUT_13") (pintype "output"))
      (node (ref "U1") (pin "14") (pinfunction "~{RESET}_14") (pintype "input"))
    )
    (net (code "35") (name "Net-(U1-USBDM)") (class "Default")
      (node (ref "R13") (pin "2") (pinfunction "2_2") (pintype "passive"))
      (node (ref "U1") (pin "12") (pinfunction "USBDM_12") (pintype "input"))
    )
    (net (code "36") (name "Net-(U1-USBDP)") (class "Default")
      (node (ref "R14") (pin "2") (pinfunction "2_2") (pintype "passive"))
      (node (ref "U1") (pin "11") (pinfunction "USBDP_11") (pintype "input"))
    )
    (net (code "37") (name "Net-(U2-PROG)") (class "Default")
      (node (ref "R9") (pin "1") (pinfunction "1_1") (pintype "passive"))
      (node (ref "U2") (pin "5") (pinfunction "PROG_5") (pintype "input"))
    )
    (net (code "38") (name "Net-(U2-STAT)") (class "Default")
      (node (ref "R8") (pin "1") (pinfunction "1_1") (pintype "passive"))
      (node (ref "U2") (pin "1") (pinfunction "STAT_1") (pintype "output"))
    )
    (net (code "39") (name "VBAT") (class "Default")
      (node (ref "C5") (pin "1") (pinfunction "1_1") (pintype "passive"))
      (node (ref "Q1") (pin "3") (pinfunction "D_3") (pintype "passive"))
      (node (ref "TP16") (pin "TP") (pinfunction "TP_TP") (pintype "input"))
      (node (ref "U2") (pin "3") (pinfunction "VBAT_3") (pintype "power_in"))
      (node (ref "X3") (pin "1@1") (pinfunction "P$1_1@1") (pintype "bidirectional"))
      (node (ref "X3") (pin "1@2") (pinfunction "P$1_1@2") (pintype "bidirectional"))
    )
    (net (code "40") (name "VCC") (class "Default")
      (node (ref "C11") (pin "+") (pinfunction "+_+") (pintype "passive"))
      (node (ref "C2") (pin "1") (pinfunction "1_1") (pintype "passive"))
      (node (ref "C3") (pin "1") (pinfunction "1_1") (pintype "passive"))
      (node (ref "C4") (pin "1") (pinfunction "1_1") (pintype "passive"))
      (node (ref "C6") (pin "1") (pinfunction "1_1") (pintype "passive"))
      (node (ref "C9") (pin "1") (pinfunction "1_1") (pintype "passive"))
      (node (ref "LED1") (pin "4") (pinfunction "VDD_4") (pintype "bidirectional"))
      (node (ref "LED2") (pin "4") (pinfunction "VDD_4") (pintype "bidirectional"))
      (node (ref "R12") (pin "1") (pinfunction "1_1") (pintype "passive"))
      (node (ref "R7") (pin "2") (pinfunction "2_2") (pintype "passive"))
      (node (ref "TP15") (pin "TP") (pinfunction "TP_TP") (pintype "input"))
      (node (ref "U1") (pin "3") (pinfunction "VCCIO_3") (pintype "power_in"))
      (node (ref "U3") (pin "CH_PD") (pinfunction "CH_PD_CH_PD") (pintype "bidirectional"))
      (node (ref "U3") (pin "VCC") (pinfunction "VCC_VCC") (pintype "bidirectional"))
      (node (ref "U4") (pin "5") (pinfunction "OUT_5") (pintype "passive"))
    )
    (net (code "41") (name "VIN") (class "Default")
      (node (ref "C7") (pin "1") (pinfunction "1_1") (pintype "passive"))
      (node (ref "D2") (pin "C") (pinfunction "C_C") (pintype "passive"))
      (node (ref "D3") (pin "C") (pinfunction "C_C") (pintype "passive"))
      (node (ref "Q1") (pin "2") (pinfunction "S_2") (pintype "passive"))
      (node (ref "SW9") (pin "3") (pinfunction "S_3") (pintype "passive"))
      (node (ref "U4") (pin "1") (pinfunction "IN_1") (pintype "input"))
    )
    (net (code "42") (name "unconnected-(LED2-COUT-Pad5)") (class "Default")
      (node (ref "LED2") (pin "5") (pinfunction "COUT_5") (pintype "output"))
    )
    (net (code "43") (name "unconnected-(LED2-DOUT-Pad6)") (class "Default")
      (node (ref "LED2") (pin "6") (pinfunction "DOUT_6") (pintype "output"))
    )
    (net (code "44") (name "unconnected-(SW1-A1-PadA@2)") (class "Default")
      (node (ref "SW1") (pin "A@2") (pinfunction "A1_A@2") (pintype "bidirectional"))
    )
    (net (code "45") (name "unconnected-(SW1-B1-PadB@2)") (class "Default")
      (node (ref "SW1") (pin "B@2") (pinfunction "B1_B@2") (pintype "bidirectional"))
    )
    (net (code "46") (name "unconnected-(SW2-A1-PadA@2)") (class "Default")
      (node (ref "SW2") (pin "A@2") (pinfunction "A1_A@2") (pintype "bidirectional"))
    )
    (net (code "47") (name "unconnected-(SW2-B1-PadB@2)") (class "Default")
      (node (ref "SW2") (pin "B@2") (pinfunction "B1_B@2") (pintype "bidirectional"))
    )
    (net (code "48") (name "unconnected-(SW3-A1-PadA@2)") (class "Default")
      (node (ref "SW3") (pin "A@2") (pinfunction "A1_A@2") (pintype "bidirectional"))
    )
    (net (code "49") (name "unconnected-(SW3-B1-PadB@2)") (class "Default")
      (node (ref "SW3") (pin "B@2") (pinfunction "B1_B@2") (pintype "bidirectional"))
    )
    (net (code "50") (name "unconnected-(SW4-A1-PadA@2)") (class "Default")
      (node (ref "SW4") (pin "A@2") (pinfunction "A1_A@2") (pintype "bidirectional"))
    )
    (net (code "51") (name "unconnected-(SW4-B1-PadB@2)") (class "Default")
      (node (ref "SW4") (pin "B@2") (pinfunction "B1_B@2") (pintype "bidirectional"))
    )
    (net (code "52") (name "unconnected-(SW5-A1-PadA@2)") (class "Default")
      (node (ref "SW5") (pin "A@2") (pinfunction "A1_A@2") (pintype "bidirectional"))
    )
    (net (code "53") (name "unconnected-(SW5-B1-PadB@2)") (class "Default")
      (node (ref "SW5") (pin "B@2") (pinfunction "B1_B@2") (pintype "bidirectional"))
    )
    (net (code "54") (name "unconnected-(SW6-A1-PadA@2)") (class "Default")
      (node (ref "SW6") (pin "A@2") (pinfunction "A1_A@2") (pintype "bidirectional"))
    )
    (net (code "55") (name "unconnected-(SW6-B1-PadB@2)") (class "Default")
      (node (ref "SW6") (pin "B@2") (pinfunction "B1_B@2") (pintype "bidirectional"))
    )
    (net (code "56") (name "unconnected-(SW7-A1-PadA@2)") (class "Default")
      (node (ref "SW7") (pin "A@2") (pinfunction "A1_A@2") (pintype "bidirectional"))
    )
    (net (code "57") (name "unconnected-(SW7-B1-PadB@2)") (class "Default")
      (node (ref "SW7") (pin "B@2") (pinfunction "B1_B@2") (pintype "bidirectional"))
    )
    (net (code "58") (name "unconnected-(SW8-A-PadA@1)") (class "Default")
      (node (ref "SW8") (pin "A@1") (pinfunction "A_A@1") (pintype "bidirectional"))
    )
    (net (code "59") (name "unconnected-(SW8-B-PadB@1)") (class "Default")
      (node (ref "SW8") (pin "B@1") (pinfunction "B_B@1") (pintype "bidirectional"))
    )
    (net (code "60") (name "unconnected-(U1-CBUS0-Pad18)") (class "Default")
      (node (ref "U1") (pin "18") (pinfunction "CBUS0_18") (pintype "bidirectional"))
    )
    (net (code "61") (name "unconnected-(U1-CBUS1-Pad17)") (class "Default")
      (node (ref "U1") (pin "17") (pinfunction "CBUS1_17") (pintype "bidirectional"))
    )
    (net (code "62") (name "unconnected-(U1-CBUS2-Pad10)") (class "Default")
      (node (ref "U1") (pin "10") (pinfunction "CBUS2_10") (pintype "bidirectional"))
    )
    (net (code "63") (name "unconnected-(U1-CBUS3-Pad19)") (class "Default")
      (node (ref "U1") (pin "19") (pinfunction "CBUS3_19") (pintype "bidirectional"))
    )
    (net (code "64") (name "unconnected-(U1-~{DCD}-Pad8)") (class "Default")
      (node (ref "U1") (pin "8") (pinfunction "~{DCD}_8") (pintype "input"))
    )
    (net (code "65") (name "unconnected-(U1-~{DSR}-Pad7)") (class "Default")
      (node (ref "U1") (pin "7") (pinfunction "~{DSR}_7") (pintype "input"))
    )
    (net (code "66") (name "unconnected-(U1-~{RI}-Pad5)") (class "Default")
      (node (ref "U1") (pin "5") (pinfunction "~{RI}_5") (pintype "input"))
    )
    (net (code "67") (name "unconnected-(U4-BP-Pad4)") (class "Default")
      (node (ref "U4") (pin "4") (pinfunction "BP_4") (pintype "input"))
    )
    (net (code "68") (name "unconnected-(X1-ID-PadID1)") (class "Default")
      (node (ref "X1") (pin "ID1") (pinfunction "ID_ID1") (pintype "bidirectional"))
    )
  )
)
